# rl78l1a_smart_blood_pressure_monitor_sch.net
KiCad netlist of a schematic drawn in Altium Designer
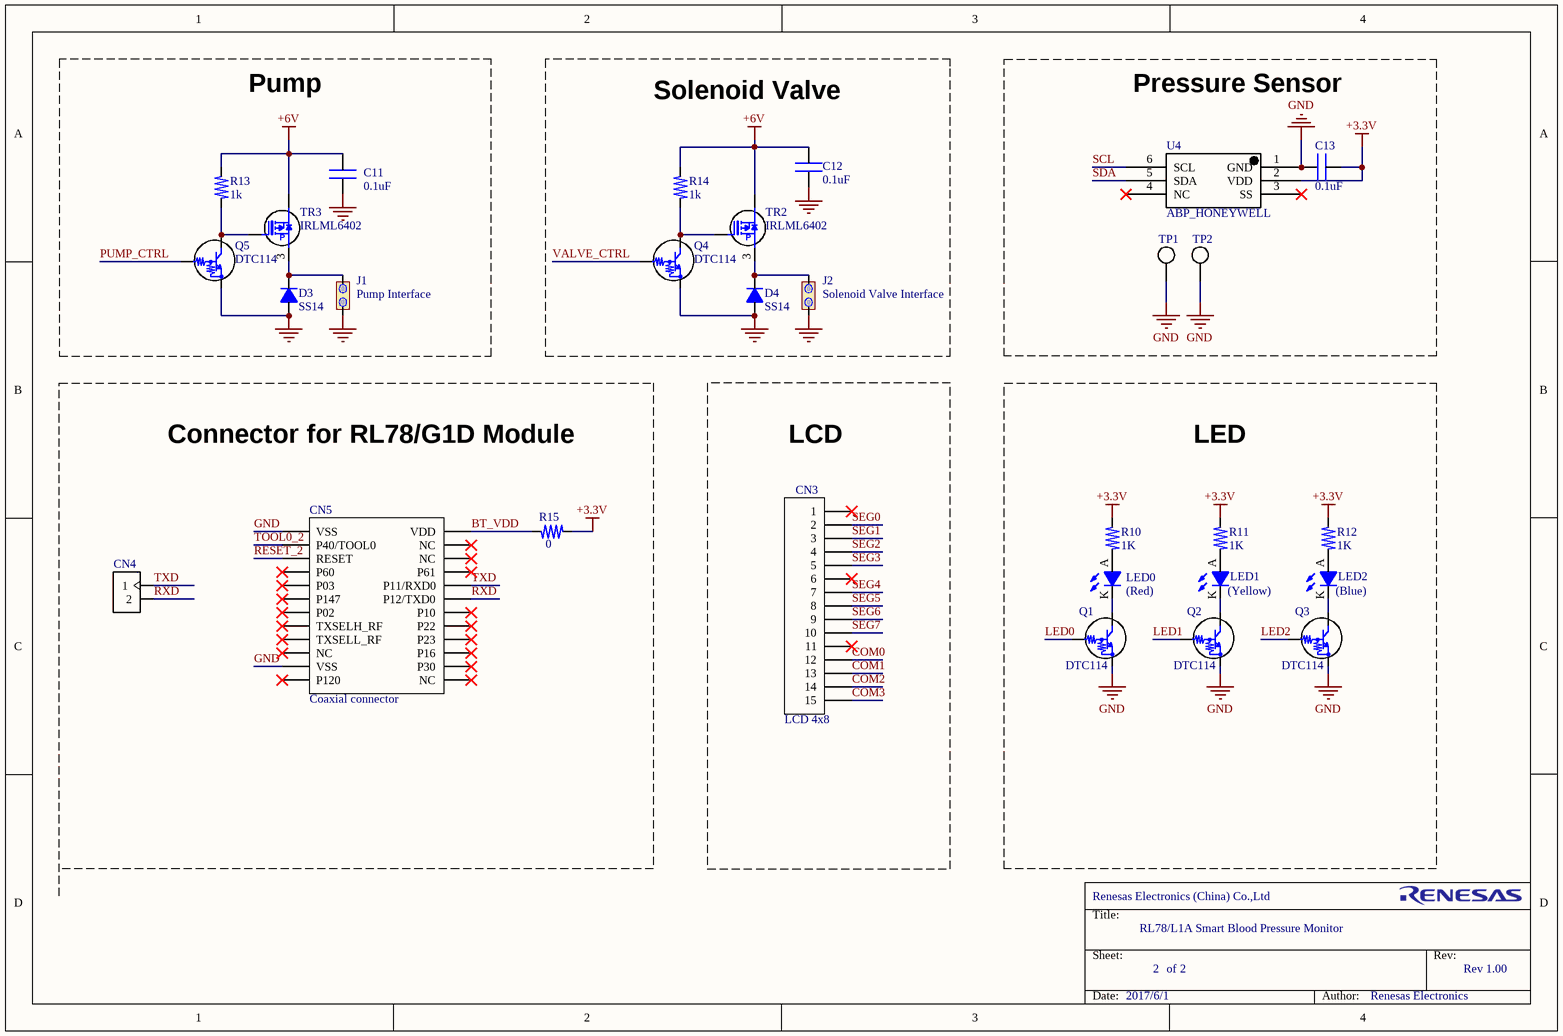
[diagram p0: rl78l1a_smart_blood_pressure_monitor_sch2.SchDoc]

(export (version "E")
  (design (tool "Eeschema 10.0.6"))
  (components
    (comp (ref "C11") (value "0.1uF") (footprint "0805") (libsource (lib "R8CLXSLP") (part "CAP")))
    (comp (ref "C12") (value "0.1uF") (footprint "0805") (libsource (lib "Sphygmometer") (part "CAP")))
    (comp (ref "C13") (value "0.1uF") (footprint "0805") (libsource (lib "分立元件") (part "CAP")))
    (comp (ref "CN3")
      (value "LCD 4x8")
      (footprint "LCD 4X8")
      (libsource (lib "PCB_Project1") (part "LCD 4x8"))
    )
    (comp (ref "CN4")
      (value "CON 2PIN A")
      (footprint "JMP-2 A")
      (libsource (lib "插头接插件") (part "CON 2PIN A"))
    )
    (comp (ref "CN5")
      (value "Coaxial connector")
      (footprint "CRS5001 - 24")
      (fields (field (name "PUBLISHER") "Altium Limited"))
      (libsource (lib "1RMB") (part "Coaxial connector"))
    )
    (comp (ref "D3") (value "SS14") (footprint "D1N") (libsource (lib "分立元件") (part "1SS404")))
    (comp (ref "D4") (value "SS14") (footprint "D1N") (libsource (lib "分立元件") (part "1SS404")))
    (comp (ref "J1") (value "JMP 2PIN") (footprint "JMP-2 A") (libsource (lib "R8CLXSLP") (part "JMP 2PIN")))
    (comp (ref "J2") (value "JMP 2PIN") (footprint "JMP-2 A") (libsource (lib "R8CLXSLP") (part "JMP 2PIN")))
    (comp (ref "LED0") (value "~") (footprint "LED 0603") (libsource (lib "分立元件") (part "LED")))
    (comp (ref "LED1") (value "~") (footprint "LED 0603") (libsource (lib "分立元件") (part "LED")))
    (comp (ref "LED2") (value "~") (footprint "LED 0603") (libsource (lib "分立元件") (part "LED")))
    (comp (ref "Q1") (value "DTC114") (footprint "SOT-23-3 A") (libsource (lib "分立元件") (part "DTC114")))
    (comp (ref "Q2") (value "DTC114") (footprint "SOT-23-3 A") (libsource (lib "分立元件") (part "DTC114")))
    (comp (ref "Q3") (value "DTC114") (footprint "SOT-23-3 A") (libsource (lib "分立元件") (part "DTC114")))
    (comp (ref "Q4") (value "DTC114") (footprint "SOT-23-3 A") (libsource (lib "分立元件") (part "DTC114")))
    (comp (ref "Q5") (value "DTC114") (footprint "SOT-23-3 A") (libsource (lib "分立元件") (part "DTC114")))
    (comp (ref "R10") (value "1K") (footprint "0603") (libsource (lib "分立元件") (part "RES")))
    (comp (ref "R11") (value "1K") (footprint "0603") (libsource (lib "分立元件") (part "RES")))
    (comp (ref "R12") (value "1K") (footprint "0603") (libsource (lib "分立元件") (part "RES")))
    (comp (ref "R13") (value "1k") (footprint "0805") (libsource (lib "分立元件") (part "RES")))
    (comp (ref "R14") (value "1k") (footprint "0805") (libsource (lib "分立元件") (part "RES")))
    (comp (ref "R15") (value "0") (footprint "0805") (libsource (lib "分立元件") (part "RES")))
    (comp (ref "TP1") (value "~") (footprint "TP A") (libsource (lib "分立元件") (part "TP")))
    (comp (ref "TP2") (value "~") (footprint "TP A") (libsource (lib "分立元件") (part "TP")))
    (comp (ref "TR2") (value "IRLML6402") (footprint "SOT-23-3 B") (libsource (lib "开关管") (part "IRLML5103")))
    (comp (ref "TR3") (value "IRLML6402") (footprint "SOT-23-3 B") (libsource (lib "开关管") (part "IRLML5103")))
    (comp (ref "U4")
      (value "ABP_HONEYWELL")
      (footprint "ABP-DIP6")
      (libsource (lib "传感器") (part "ABP_HONEYWELL"))
    )
  )
  (nets
    (net (code "1") (name "+3.3V") (class "Default")
      (node (ref "C13") (pin "1") (pinfunction "1_1") (pintype "passive"))
      (node (ref "R10") (pin "2") (pinfunction "2_2") (pintype "passive"))
      (node (ref "R11") (pin "2") (pinfunction "2_2") (pintype "passive"))
      (node (ref "R12") (pin "2") (pinfunction "2_2") (pintype "passive"))
      (node (ref "R15") (pin "1") (pinfunction "1_1") (pintype "passive"))
      (node (ref "U4") (pin "2") (pinfunction "VDD_2") (pintype "passive"))
    )
    (net (code "2") (name "+6V") (class "Default")
      (node (ref "C11") (pin "1") (pinfunction "1_1") (pintype "passive"))
      (node (ref "C12") (pin "1") (pinfunction "1_1") (pintype "passive"))
      (node (ref "R13") (pin "1") (pinfunction "1_1") (pintype "passive"))
      (node (ref "R14") (pin "1") (pinfunction "1_1") (pintype "passive"))
      (node (ref "TR2") (pin "2") (pinfunction "S_2") (pintype "passive"))
      (node (ref "TR3") (pin "2") (pinfunction "S_2") (pintype "passive"))
    )
    (net (code "3") (name "/BT_VDD") (class "Default")
      (node (ref "CN5") (pin "2") (pinfunction "VDD_2") (pintype "passive"))
      (node (ref "R15") (pin "2") (pinfunction "2_2") (pintype "passive"))
    )
    (net (code "4") (name "/COM0") (class "Default")
      (node (ref "CN3") (pin "12") (pinfunction "12_12") (pintype "passive"))
    )
    (net (code "5") (name "/COM1") (class "Default")
      (node (ref "CN3") (pin "13") (pinfunction "13_13") (pintype "passive"))
    )
    (net (code "6") (name "/COM2") (class "Default")
      (node (ref "CN3") (pin "14") (pinfunction "14_14") (pintype "passive"))
    )
    (net (code "7") (name "/COM3") (class "Default")
      (node (ref "CN3") (pin "15") (pinfunction "15_15") (pintype "passive"))
    )
    (net (code "8") (name "/LED0") (class "Default") (node (ref "Q1") (pin "B") (pintype "passive")))
    (net (code "9") (name "/LED1") (class "Default") (node (ref "Q2") (pin "B") (pintype "passive")))
    (net (code "10") (name "/LED2") (class "Default") (node (ref "Q3") (pin "B") (pintype "passive")))
    (net (code "11") (name "/PUMP_CTRL") (class "Default") (node (ref "Q5") (pin "B") (pintype "passive")))
    (net (code "12") (name "/RESET_2") (class "Default")
      (node (ref "CN5") (pin "5") (pinfunction "RESET_5") (pintype "passive"))
    )
    (net (code "13") (name "/RXD") (class "Default")
      (node (ref "CN4") (pin "2") (pinfunction "2_2") (pintype "passive"))
      (node (ref "CN5") (pin "12") (pinfunction "P12/TXD0_12") (pintype "passive"))
    )
    (net (code "14") (name "/SCL") (class "Default")
      (node (ref "U4") (pin "6") (pinfunction "SCL_6") (pintype "passive"))
    )
    (net (code "15") (name "/SDA") (class "Default")
      (node (ref "U4") (pin "5") (pinfunction "SDA_5") (pintype "passive"))
    )
    (net (code "16") (name "/SEG0") (class "Default")
      (node (ref "CN3") (pin "2") (pinfunction "2_2") (pintype "passive"))
    )
    (net (code "17") (name "/SEG1") (class "Default")
      (node (ref "CN3") (pin "3") (pinfunction "3_3") (pintype "passive"))
    )
    (net (code "18") (name "/SEG2") (class "Default")
      (node (ref "CN3") (pin "4") (pinfunction "4_4") (pintype "passive"))
    )
    (net (code "19") (name "/SEG3") (class "Default")
      (node (ref "CN3") (pin "5") (pinfunction "5_5") (pintype "passive"))
    )
    (net (code "20") (name "/SEG4") (class "Default")
      (node (ref "CN3") (pin "7") (pinfunction "7_7") (pintype "passive"))
    )
    (net (code "21") (name "/SEG5") (class "Default")
      (node (ref "CN3") (pin "8") (pinfunction "8_8") (pintype "passive"))
    )
    (net (code "22") (name "/SEG6") (class "Default")
      (node (ref "CN3") (pin "9") (pinfunction "9_9") (pintype "passive"))
    )
    (net (code "23") (name "/SEG7") (class "Default")
      (node (ref "CN3") (pin "10") (pinfunction "10_10") (pintype "passive"))
    )
    (net (code "24") (name "/TOOL0_2") (class "Default")
      (node (ref "CN5") (pin "3") (pinfunction "P40/TOOL0_3") (pintype "passive"))
    )
    (net (code "25") (name "/TXD") (class "Default")
      (node (ref "CN4") (pin "1") (pinfunction "1_1") (pintype "passive"))
      (node (ref "CN5") (pin "10") (pinfunction "P11/RXD0_10") (pintype "passive"))
    )
    (net (code "26") (name "/VALVE_CTRL") (class "Default") (node (ref "Q4") (pin "B") (pintype "passive")))
    (net (code "27") (name "GND") (class "Default")
      (node (ref "C11") (pin "2") (pinfunction "2_2") (pintype "passive"))
      (node (ref "C12") (pin "2") (pinfunction "2_2") (pintype "passive"))
      (node (ref "C13") (pin "2") (pinfunction "2_2") (pintype "passive"))
      (node (ref "CN5") (pin "1") (pinfunction "VSS_1") (pintype "passive"))
      (node (ref "CN5") (pin "21") (pinfunction "VSS_21") (pintype "passive"))
      (node (ref "D3") (pin "A") (pinfunction "A_A") (pintype "passive"))
      (node (ref "D4") (pin "A") (pinfunction "A_A") (pintype "passive"))
      (node (ref "J1") (pin "2") (pinfunction "2_2") (pintype "passive"))
      (node (ref "J2") (pin "2") (pinfunction "2_2") (pintype "passive"))
      (node (ref "Q1") (pin "E") (pintype "passive"))
      (node (ref "Q2") (pin "E") (pintype "passive"))
      (node (ref "Q3") (pin "E") (pintype "passive"))
      (node (ref "Q4") (pin "E") (pintype "passive"))
      (node (ref "Q5") (pin "E") (pintype "passive"))
      (node (ref "TP1") (pin "1") (pinfunction "TP_1") (pintype "passive"))
      (node (ref "TP2") (pin "1") (pinfunction "TP_1") (pintype "passive"))
      (node (ref "U4") (pin "1") (pinfunction "GND_1") (pintype "passive"))
    )
    (net (code "28") (name "Net-(LED0-PadA)") (class "Default")
      (node (ref "LED0") (pin "A") (pinfunction "A_A") (pintype "passive"))
      (node (ref "R10") (pin "1") (pinfunction "1_1") (pintype "passive"))
    )
    (net (code "29") (name "Net-(LED0-PadK)") (class "Default")
      (node (ref "LED0") (pin "K") (pinfunction "K_K") (pintype "passive"))
      (node (ref "Q1") (pin "C") (pintype "passive"))
    )
    (net (code "30") (name "Net-(LED1-PadA)") (class "Default")
      (node (ref "LED1") (pin "A") (pinfunction "A_A") (pintype "passive"))
      (node (ref "R11") (pin "1") (pinfunction "1_1") (pintype "passive"))
    )
    (net (code "31") (name "Net-(LED1-PadK)") (class "Default")
      (node (ref "LED1") (pin "K") (pinfunction "K_K") (pintype "passive"))
      (node (ref "Q2") (pin "C") (pintype "passive"))
    )
    (net (code "32") (name "Net-(LED2-PadA)") (class "Default")
      (node (ref "LED2") (pin "A") (pinfunction "A_A") (pintype "passive"))
      (node (ref "R12") (pin "1") (pinfunction "1_1") (pintype "passive"))
    )
    (net (code "33") (name "Net-(LED2-PadK)") (class "Default")
      (node (ref "LED2") (pin "K") (pinfunction "K_K") (pintype "passive"))
      (node (ref "Q3") (pin "C") (pintype "passive"))
    )
    (net (code "34") (name "Net-(TR2-D)") (class "Default")
      (node (ref "D4") (pin "K") (pinfunction "K_K") (pintype "passive"))
      (node (ref "J2") (pin "1") (pinfunction "1_1") (pintype "passive"))
      (node (ref "TR2") (pin "3") (pinfunction "D_3") (pintype "passive"))
    )
    (net (code "35") (name "Net-(TR2-G)") (class "Default")
      (node (ref "Q4") (pin "C") (pintype "passive"))
      (node (ref "R14") (pin "2") (pinfunction "2_2") (pintype "passive"))
      (node (ref "TR2") (pin "1") (pinfunction "G_1") (pintype "passive"))
    )
    (net (code "36") (name "Net-(TR3-D)") (class "Default")
      (node (ref "D3") (pin "K") (pinfunction "K_K") (pintype "passive"))
      (node (ref "J1") (pin "1") (pinfunction "1_1") (pintype "passive"))
      (node (ref "TR3") (pin "3") (pinfunction "D_3") (pintype "passive"))
    )
    (net (code "37") (name "Net-(TR3-G)") (class "Default")
      (node (ref "Q5") (pin "C") (pintype "passive"))
      (node (ref "R13") (pin "2") (pinfunction "2_2") (pintype "passive"))
      (node (ref "TR3") (pin "1") (pinfunction "G_1") (pintype "passive"))
    )
    (net (code "38") (name "unconnected-(CN3-Pad1)") (class "Default")
      (node (ref "CN3") (pin "1") (pinfunction "1_1") (pintype "passive+no_connect"))
    )
    (net (code "39") (name "unconnected-(CN3-Pad6)") (class "Default")
      (node (ref "CN3") (pin "6") (pinfunction "6_6") (pintype "passive+no_connect"))
    )
    (net (code "40") (name "unconnected-(CN3-Pad11)") (class "Default")
      (node (ref "CN3") (pin "11") (pinfunction "11_11") (pintype "passive+no_connect"))
    )
    (net (code "41") (name "unconnected-(CN5-NC-Pad4)") (class "Default")
      (node (ref "CN5") (pin "4") (pinfunction "NC_4") (pintype "passive+no_connect"))
    )
    (net (code "42") (name "unconnected-(CN5-NC-Pad6)") (class "Default")
      (node (ref "CN5") (pin "6") (pinfunction "NC_6") (pintype "passive+no_connect"))
    )
    (net (code "43") (name "unconnected-(CN5-NC-Pad19)") (class "Default")
      (node (ref "CN5") (pin "19") (pinfunction "NC_19") (pintype "passive+no_connect"))
    )
    (net (code "44") (name "unconnected-(CN5-NC-Pad24)") (class "Default")
      (node (ref "CN5") (pin "24") (pinfunction "NC_24") (pintype "passive+no_connect"))
    )
    (net (code "45") (name "unconnected-(CN5-P02-Pad13)") (class "Default")
      (node (ref "CN5") (pin "13") (pinfunction "P02_13") (pintype "passive+no_connect"))
    )
    (net (code "46") (name "unconnected-(CN5-P03-Pad9)") (class "Default")
      (node (ref "CN5") (pin "9") (pinfunction "P03_9") (pintype "passive+no_connect"))
    )
    (net (code "47") (name "unconnected-(CN5-P10-Pad14)") (class "Default")
      (node (ref "CN5") (pin "14") (pinfunction "P10_14") (pintype "passive+no_connect"))
    )
    (net (code "48") (name "unconnected-(CN5-P16-Pad20)") (class "Default")
      (node (ref "CN5") (pin "20") (pinfunction "P16_20") (pintype "passive+no_connect"))
    )
    (net (code "49") (name "unconnected-(CN5-P22-Pad16)") (class "Default")
      (node (ref "CN5") (pin "16") (pinfunction "P22_16") (pintype "passive+no_connect"))
    )
    (net (code "50") (name "unconnected-(CN5-P23-Pad18)") (class "Default")
      (node (ref "CN5") (pin "18") (pinfunction "P23_18") (pintype "passive+no_connect"))
    )
    (net (code "51") (name "unconnected-(CN5-P30-Pad22)") (class "Default")
      (node (ref "CN5") (pin "22") (pinfunction "P30_22") (pintype "passive+no_connect"))
    )
    (net (code "52") (name "unconnected-(CN5-P60-Pad7)") (class "Default")
      (node (ref "CN5") (pin "7") (pinfunction "P60_7") (pintype "passive+no_connect"))
    )
    (net (code "53") (name "unconnected-(CN5-P61-Pad8)") (class "Default")
      (node (ref "CN5") (pin "8") (pinfunction "P61_8") (pintype "passive+no_connect"))
    )
    (net (code "54") (name "unconnected-(CN5-P120-Pad23)") (class "Default")
      (node (ref "CN5") (pin "23") (pinfunction "P120_23") (pintype "passive+no_connect"))
    )
    (net (code "55") (name "unconnected-(CN5-P147-Pad11)") (class "Default")
      (node (ref "CN5") (pin "11") (pinfunction "P147_11") (pintype "passive+no_connect"))
    )
    (net (code "56") (name "unconnected-(CN5-TXSELH_RF-Pad15)") (class "Default")
      (node (ref "CN5") (pin "15") (pinfunction "TXSELH_RF_15") (pintype "passive+no_connect"))
    )
    (net (code "57") (name "unconnected-(CN5-TXSELL_RF-Pad17)") (class "Default")
      (node (ref "CN5") (pin "17") (pinfunction "TXSELL_RF_17") (pintype "passive+no_connect"))
    )
    (net (code "58") (name "unconnected-(U4-NC-Pad4)") (class "Default")
      (node (ref "U4") (pin "4") (pinfunction "NC_4") (pintype "passive+no_connect"))
    )
    (net (code "59") (name "unconnected-(U4-SS-Pad3)") (class "Default")
      (node (ref "U4") (pin "3") (pinfunction "SS_3") (pintype "passive+no_connect"))
    )
  )
)
